# Lamp_Logic_Board_4.net
KiCad netlist of a schematic drawn in EAGLE
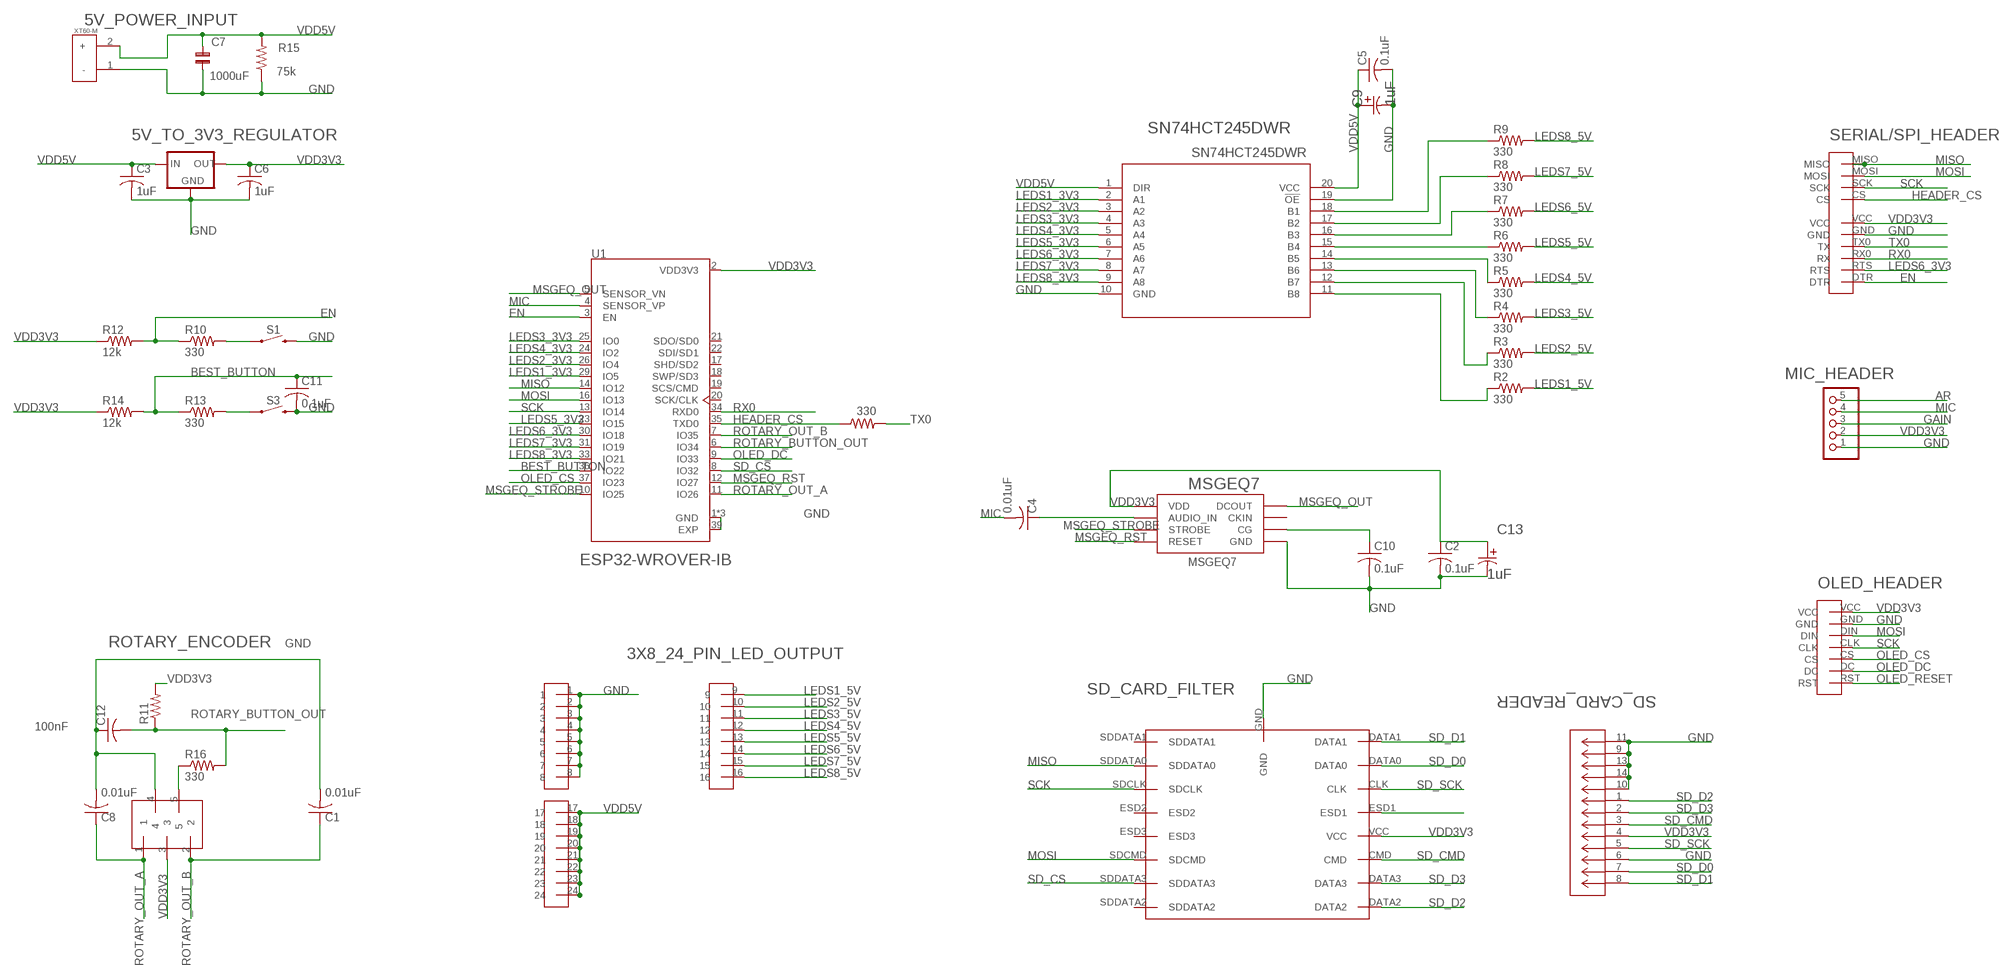
[diagram p0: schematic, sheet 1]

(export (version "E")
  (design (tool "Eeschema 10.0.6"))
  (components
    (comp (ref "3X8_24_PIN_LED_OUTPUT")
      (value "3X8PINHEAD")
      (footprint "eagle-import:3X8PINHEAD")
      (libsource (lib "eagle-import") (part "3X8PINHEAD"))
    )
    (comp (ref "5V_POWER_INPUT")
      (value "XT60-M")
      (footprint "eagle-import:AMASS_XT60-M")
      (fields (field (name "MF") "AMASS"))
      (libsource (lib "eagle-import") (part "XT60-M"))
    )
    (comp (ref "5V_TO_3V3_REGULATOR")
      (value "LM1117MP-1.8")
      (footprint "eagle-import:SOT223")
      (fields (field (name "MF") "Texas Instruments"))
      (libsource (lib "eagle-import") (part "LM1117?-MP1.8"))
    )
    (comp (ref "C1")
      (value "0.01uF")
      (footprint "eagle-import:C0402")
      (libsource (lib "eagle-import") (part "C-USC0402"))
    )
    (comp (ref "C2")
      (value "0.1uF")
      (footprint "eagle-import:C0805")
      (libsource (lib "eagle-import") (part "C-USC0805"))
    )
    (comp (ref "C3")
      (value "1uF")
      (footprint "eagle-import:C0402")
      (libsource (lib "eagle-import") (part "C-USC0402"))
    )
    (comp (ref "C4")
      (value "0.01uF")
      (footprint "eagle-import:C0402")
      (libsource (lib "eagle-import") (part "C-USC0402"))
    )
    (comp (ref "C5")
      (value "0.1uF")
      (footprint "eagle-import:C0805")
      (libsource (lib "eagle-import") (part "C-USC0805"))
    )
    (comp (ref "C6")
      (value "1uF")
      (footprint "eagle-import:C0402")
      (libsource (lib "eagle-import") (part "C-USC0402"))
    )
    (comp (ref "C7")
      (value "1000uF")
      (footprint "eagle-import:ENP2,0-5")
      (libsource (lib "eagle-import") (part "C-BP-2,0X5"))
    )
    (comp (ref "C8")
      (value "0.01uF")
      (footprint "eagle-import:C0402")
      (libsource (lib "eagle-import") (part "C-USC0402"))
    )
    (comp (ref "C9")
      (value "1uF")
      (footprint "eagle-import:CAP_EEFC_B")
      (fields (field (name "MANUFACTURER_PART_NUMBER") "EEEFC1V1R0R"))
      (libsource (lib "eagle-import") (part "EEEFC1V1R0R"))
    )
    (comp (ref "C10")
      (value "0.1uF")
      (footprint "eagle-import:C0805")
      (libsource (lib "eagle-import") (part "C-USC0805"))
    )
    (comp (ref "C11")
      (value "0.1uF")
      (footprint "eagle-import:C0805")
      (libsource (lib "eagle-import") (part "C-USC0805"))
    )
    (comp (ref "C12")
      (value "100nF")
      (footprint "eagle-import:C0402")
      (libsource (lib "eagle-import") (part "C-USC0402"))
    )
    (comp (ref "C13")
      (value "1uF")
      (footprint "eagle-import:CAP_EEFC_B")
      (fields (field (name "MANUFACTURER_PART_NUMBER") "EEEFC1V1R0R"))
      (libsource (lib "eagle-import") (part "EEEFC1V1R0R"))
    )
    (comp (ref "MIC_HEADER")
      (value "PINHD-1X5")
      (footprint "eagle-import:1X05")
      (libsource (lib "eagle-import") (part "PINHD-1X5"))
    )
    (comp (ref "MSGEQ7")
      (value "MSGEQ7DIL")
      (footprint "eagle-import:DIL-08")
      (fields
        (field (name "DIGI-KEY_PART_NUMBER") "1568-1544-ND")
        (field (name "MF") "SparkFun Electronics")
        (field (name "MP") "MSGEQ7")
      )
      (libsource (lib "eagle-import") (part "MSGEQ7DIL"))
    )
    (comp (ref "OLED_HEADER")
      (value "SPIOLED_STANDOFF")
      (footprint "eagle-import:SPIOLED_STADOFF")
      (libsource (lib "eagle-import") (part "SPIOLED_STANDOFF"))
    )
    (comp (ref "R1")
      (value "330")
      (footprint "eagle-import:R1206")
      (libsource (lib "eagle-import") (part "R-US_R1206"))
    )
    (comp (ref "R2")
      (value "330")
      (footprint "eagle-import:R1206")
      (libsource (lib "eagle-import") (part "R-US_R1206"))
    )
    (comp (ref "R3")
      (value "330")
      (footprint "eagle-import:R1206")
      (libsource (lib "eagle-import") (part "R-US_R1206"))
    )
    (comp (ref "R4")
      (value "330")
      (footprint "eagle-import:R1206")
      (libsource (lib "eagle-import") (part "R-US_R1206"))
    )
    (comp (ref "R5")
      (value "330")
      (footprint "eagle-import:R1206")
      (libsource (lib "eagle-import") (part "R-US_R1206"))
    )
    (comp (ref "R6")
      (value "330")
      (footprint "eagle-import:R1206")
      (libsource (lib "eagle-import") (part "R-US_R1206"))
    )
    (comp (ref "R7")
      (value "330")
      (footprint "eagle-import:R1206")
      (libsource (lib "eagle-import") (part "R-US_R1206"))
    )
    (comp (ref "R8")
      (value "330")
      (footprint "eagle-import:R1206")
      (libsource (lib "eagle-import") (part "R-US_R1206"))
    )
    (comp (ref "R9")
      (value "330")
      (footprint "eagle-import:R1206")
      (libsource (lib "eagle-import") (part "R-US_R1206"))
    )
    (comp (ref "R10")
      (value "330")
      (footprint "eagle-import:R1206")
      (libsource (lib "eagle-import") (part "R-US_R1206"))
    )
    (comp (ref "R11")
      (value "R-US_R0603")
      (footprint "eagle-import:R0603")
      (libsource (lib "eagle-import") (part "R-US_R0603"))
    )
    (comp (ref "R12")
      (value "12k")
      (footprint "eagle-import:R0603")
      (libsource (lib "eagle-import") (part "R-US_R0603"))
    )
    (comp (ref "R13")
      (value "330")
      (footprint "eagle-import:R1206")
      (libsource (lib "eagle-import") (part "R-US_R1206"))
    )
    (comp (ref "R14")
      (value "12k")
      (footprint "eagle-import:R0603")
      (libsource (lib "eagle-import") (part "R-US_R0603"))
    )
    (comp (ref "R15")
      (value "75k")
      (footprint "eagle-import:0309_12")
      (libsource (lib "eagle-import") (part "R-US_0309/12"))
    )
    (comp (ref "R16")
      (value "330")
      (footprint "eagle-import:R1206")
      (libsource (lib "eagle-import") (part "R-US_R1206"))
    )
    (comp (ref "ROTARY_ENCODER")
      (value "EN11-HSM1AF15")
      (footprint "eagle-import:EN11-HSM")
      (libsource (lib "eagle-import") (part "EN11-HSM1AF15"))
    )
    (comp (ref "S1")
      (value "MOMENTARY-SWITCH-SPST-SMD-6.0X3.5MM")
      (footprint "eagle-import:TACTILE_SWITCH_SMD_6.0X3.5MM")
      (libsource (lib "eagle-import") (part "MOMENTARY-SWITCH-SPST-SMD-6.0X3.5MM"))
    )
    (comp (ref "S3")
      (value "MOMENTARY-SWITCH-SPST-SMD-12MM")
      (footprint "eagle-import:TACTILE_SWITCH_SMD_12MM")
      (libsource (lib "eagle-import") (part "MOMENTARY-SWITCH-SPST-SMD-12MM"))
    )
    (comp (ref "SD_CARD_FILTER")
      (value "CM1624-08DE")
      (footprint "eagle-import:CM1624-08DE")
      (libsource (lib "eagle-import") (part "CM1624-08DE"))
    )
    (comp (ref "SD_CARD_READER")
      (value "LLC")
      (footprint "eagle-import:CON00218_8")
      (libsource (lib "eagle-import") (part "LLC"))
    )
    (comp (ref "SERIAL/SPI_HEADER")
      (value "2X6PINHEAD")
      (footprint "eagle-import:2X6PINHEAD")
      (libsource (lib "eagle-import") (part "2X6PINHEAD"))
    )
    (comp (ref "SN74HCT245DWR")
      (value "SN74HCT245DWR")
      (footprint "eagle-import:DW20")
      (libsource (lib "eagle-import") (part "SN74HCT245DWR"))
    )
    (comp (ref "U1")
      (value "ESP32-WROVER-IB")
      (footprint "eagle-import:XCVR_ESP32-WROVER-I")
      (fields (field (name "MF") "Espressif Systems") (field (name "MP") "ESP32-WROVER-I"))
      (libsource (lib "eagle-import") (part "ESP32-WROVER-I"))
    )
  )
  (nets
    (net (code "1") (name "AR") (class "Default")
      (node (ref "MIC_HEADER") (pin "5") (pinfunction "5_5") (pintype "passive"))
    )
    (net (code "2") (name "BEST_BUTTON") (class "Default")
      (node (ref "C11") (pin "1") (pinfunction "1_1") (pintype "passive"))
      (node (ref "R13") (pin "1") (pinfunction "1_1") (pintype "passive"))
      (node (ref "R14") (pin "2") (pinfunction "2_2") (pintype "passive"))
      (node (ref "U1") (pin "36") (pinfunction "IO22_36") (pintype "bidirectional"))
    )
    (net (code "3") (name "EN") (class "Default")
      (node (ref "R10") (pin "1") (pinfunction "1_1") (pintype "passive"))
      (node (ref "R12") (pin "2") (pinfunction "2_2") (pintype "passive"))
      (node (ref "SERIAL/SPI_HEADER") (pin "DTR") (pinfunction "DTR_DTR") (pintype "bidirectional"))
      (node (ref "U1") (pin "3") (pinfunction "EN_3") (pintype "input"))
    )
    (net (code "4") (name "GAIN") (class "Default")
      (node (ref "MIC_HEADER") (pin "3") (pinfunction "3_3") (pintype "passive"))
    )
    (net (code "5") (name "GND") (class "Default")
      (node (ref "3X8_24_PIN_LED_OUTPUT") (pin "1") (pinfunction "1_1") (pintype "bidirectional"))
      (node (ref "3X8_24_PIN_LED_OUTPUT") (pin "2") (pinfunction "2_2") (pintype "bidirectional"))
      (node (ref "3X8_24_PIN_LED_OUTPUT") (pin "3") (pinfunction "3_3") (pintype "bidirectional"))
      (node (ref "3X8_24_PIN_LED_OUTPUT") (pin "4") (pinfunction "4_4") (pintype "bidirectional"))
      (node (ref "3X8_24_PIN_LED_OUTPUT") (pin "5") (pinfunction "5_5") (pintype "bidirectional"))
      (node (ref "3X8_24_PIN_LED_OUTPUT") (pin "6") (pinfunction "6_6") (pintype "bidirectional"))
      (node (ref "3X8_24_PIN_LED_OUTPUT") (pin "7") (pinfunction "7_7") (pintype "bidirectional"))
      (node (ref "3X8_24_PIN_LED_OUTPUT") (pin "8") (pinfunction "8_8") (pintype "bidirectional"))
      (node (ref "5V_POWER_INPUT") (pin "1") (pinfunction "-_1") (pintype "passive"))
      (node (ref "5V_TO_3V3_REGULATOR") (pin "1") (pinfunction "GND_1") (pintype "input"))
      (node (ref "C1") (pin "2") (pinfunction "2_2") (pintype "passive"))
      (node (ref "C10") (pin "2") (pinfunction "2_2") (pintype "passive"))
      (node (ref "C11") (pin "2") (pinfunction "2_2") (pintype "passive"))
      (node (ref "C12") (pin "1") (pinfunction "1_1") (pintype "passive"))
      (node (ref "C13") (pin "2") (pinfunction "2_2") (pintype "passive"))
      (node (ref "C2") (pin "2") (pinfunction "2_2") (pintype "passive"))
      (node (ref "C3") (pin "2") (pinfunction "2_2") (pintype "passive"))
      (node (ref "C5") (pin "2") (pinfunction "2_2") (pintype "passive"))
      (node (ref "C6") (pin "2") (pinfunction "2_2") (pintype "passive"))
      (node (ref "C7") (pin "1") (pinfunction "1_1") (pintype "passive"))
      (node (ref "C8") (pin "2") (pinfunction "2_2") (pintype "passive"))
      (node (ref "C9") (pin "2") (pinfunction "2_2") (pintype "passive"))
      (node (ref "MIC_HEADER") (pin "1") (pinfunction "1_1") (pintype "passive"))
      (node (ref "MSGEQ7") (pin "2") (pinfunction "GND_2") (pintype "bidirectional"))
      (node (ref "OLED_HEADER") (pin "GND") (pinfunction "GND_GND") (pintype "bidirectional"))
      (node (ref "R15") (pin "1") (pinfunction "1_1") (pintype "passive"))
      (node (ref "ROTARY_ENCODER") (pin "4") (pinfunction "4_4") (pintype "bidirectional"))
      (node (ref "S1") (pin "2") (pinfunction "2_2") (pintype "passive"))
      (node (ref "S3") (pin "3") (pinfunction "2_3") (pintype "passive"))
      (node (ref "SD_CARD_FILTER") (pin "GND") (pinfunction "GND_GND") (pintype "bidirectional"))
      (node (ref "SD_CARD_READER") (pin "10") (pinfunction "10_10") (pintype "passive"))
      (node (ref "SD_CARD_READER") (pin "11") (pinfunction "11_11") (pintype "passive"))
      (node (ref "SD_CARD_READER") (pin "13") (pinfunction "13_13") (pintype "passive"))
      (node (ref "SD_CARD_READER") (pin "14") (pinfunction "14_14") (pintype "passive"))
      (node (ref "SD_CARD_READER") (pin "6") (pinfunction "6_6") (pintype "passive"))
      (node (ref "SD_CARD_READER") (pin "9") (pinfunction "9_9") (pintype "passive"))
      (node (ref "SERIAL/SPI_HEADER") (pin "GND") (pinfunction "GND_GND") (pintype "bidirectional"))
      (node (ref "SN74HCT245DWR") (pin "10") (pinfunction "GND_10") (pintype "power_in"))
      (node (ref "SN74HCT245DWR") (pin "19") (pinfunction "~{OE}_19") (pintype "input"))
      (node (ref "U1") (pin "1") (pinfunction "GND_1") (pintype "power_in"))
      (node (ref "U1") (pin "15") (pinfunction "GND_15") (pintype "power_in"))
      (node (ref "U1") (pin "38") (pinfunction "GND_38") (pintype "power_in"))
      (node (ref "U1") (pin "39") (pinfunction "EXP_39") (pintype "power_in"))
    )
    (net (code "6") (name "HEADER_CS") (class "Default")
      (node (ref "R1") (pin "1") (pinfunction "1_1") (pintype "passive"))
      (node (ref "SERIAL/SPI_HEADER") (pin "CS") (pinfunction "CS_CS") (pintype "bidirectional"))
      (node (ref "U1") (pin "35") (pinfunction "TXD0_35") (pintype "bidirectional"))
    )
    (net (code "7") (name "LEDS1_3V3") (class "Default")
      (node (ref "SN74HCT245DWR") (pin "2") (pinfunction "A1_2") (pintype "bidirectional"))
      (node (ref "U1") (pin "29") (pinfunction "IO5_29") (pintype "bidirectional"))
    )
    (net (code "8") (name "LEDS1_5V") (class "Default")
      (node (ref "3X8_24_PIN_LED_OUTPUT") (pin "9") (pinfunction "9_9") (pintype "bidirectional"))
      (node (ref "R2") (pin "2") (pinfunction "2_2") (pintype "passive"))
    )
    (net (code "9") (name "LEDS2_3V3") (class "Default")
      (node (ref "SN74HCT245DWR") (pin "3") (pinfunction "A2_3") (pintype "bidirectional"))
      (node (ref "U1") (pin "26") (pinfunction "IO4_26") (pintype "bidirectional"))
    )
    (net (code "10") (name "LEDS2_5V") (class "Default")
      (node (ref "3X8_24_PIN_LED_OUTPUT") (pin "10") (pinfunction "10_10") (pintype "bidirectional"))
      (node (ref "R3") (pin "2") (pinfunction "2_2") (pintype "passive"))
    )
    (net (code "11") (name "LEDS3_3V3") (class "Default")
      (node (ref "SN74HCT245DWR") (pin "4") (pinfunction "A3_4") (pintype "bidirectional"))
      (node (ref "U1") (pin "25") (pinfunction "IO0_25") (pintype "bidirectional"))
    )
    (net (code "12") (name "LEDS3_5V") (class "Default")
      (node (ref "3X8_24_PIN_LED_OUTPUT") (pin "11") (pinfunction "11_11") (pintype "bidirectional"))
      (node (ref "R4") (pin "2") (pinfunction "2_2") (pintype "passive"))
    )
    (net (code "13") (name "LEDS4_3V3") (class "Default")
      (node (ref "SN74HCT245DWR") (pin "5") (pinfunction "A4_5") (pintype "bidirectional"))
      (node (ref "U1") (pin "24") (pinfunction "IO2_24") (pintype "bidirectional"))
    )
    (net (code "14") (name "LEDS4_5V") (class "Default")
      (node (ref "3X8_24_PIN_LED_OUTPUT") (pin "12") (pinfunction "12_12") (pintype "bidirectional"))
      (node (ref "R5") (pin "2") (pinfunction "2_2") (pintype "passive"))
    )
    (net (code "15") (name "LEDS5_3V3") (class "Default")
      (node (ref "SN74HCT245DWR") (pin "6") (pinfunction "A5_6") (pintype "bidirectional"))
      (node (ref "U1") (pin "23") (pinfunction "IO15_23") (pintype "bidirectional"))
    )
    (net (code "16") (name "LEDS5_5V") (class "Default")
      (node (ref "3X8_24_PIN_LED_OUTPUT") (pin "13") (pinfunction "13_13") (pintype "bidirectional"))
      (node (ref "R6") (pin "2") (pinfunction "2_2") (pintype "passive"))
    )
    (net (code "17") (name "LEDS6_3V3") (class "Default")
      (node (ref "SERIAL/SPI_HEADER") (pin "RTS") (pinfunction "RTS_RTS") (pintype "bidirectional"))
      (node (ref "SN74HCT245DWR") (pin "7") (pinfunction "A6_7") (pintype "bidirectional"))
      (node (ref "U1") (pin "30") (pinfunction "IO18_30") (pintype "bidirectional"))
    )
    (net (code "18") (name "LEDS6_5V") (class "Default")
      (node (ref "3X8_24_PIN_LED_OUTPUT") (pin "14") (pinfunction "14_14") (pintype "bidirectional"))
      (node (ref "R7") (pin "2") (pinfunction "2_2") (pintype "passive"))
    )
    (net (code "19") (name "LEDS7_3V3") (class "Default")
      (node (ref "SN74HCT245DWR") (pin "8") (pinfunction "A7_8") (pintype "bidirectional"))
      (node (ref "U1") (pin "31") (pinfunction "IO19_31") (pintype "bidirectional"))
    )
    (net (code "20") (name "LEDS7_5V") (class "Default")
      (node (ref "3X8_24_PIN_LED_OUTPUT") (pin "15") (pinfunction "15_15") (pintype "bidirectional"))
      (node (ref "R8") (pin "2") (pinfunction "2_2") (pintype "passive"))
    )
    (net (code "21") (name "LEDS8_3V3") (class "Default")
      (node (ref "SN74HCT245DWR") (pin "9") (pinfunction "A8_9") (pintype "bidirectional"))
      (node (ref "U1") (pin "33") (pinfunction "IO21_33") (pintype "bidirectional"))
    )
    (net (code "22") (name "LEDS8_5V") (class "Default")
      (node (ref "3X8_24_PIN_LED_OUTPUT") (pin "16") (pinfunction "16_16") (pintype "bidirectional"))
      (node (ref "R9") (pin "2") (pinfunction "2_2") (pintype "passive"))
    )
    (net (code "23") (name "MIC") (class "Default")
      (node (ref "C4") (pin "2") (pinfunction "2_2") (pintype "passive"))
      (node (ref "MIC_HEADER") (pin "4") (pinfunction "4_4") (pintype "passive"))
      (node (ref "U1") (pin "4") (pinfunction "SENSOR_VP_4") (pintype "input"))
    )
    (net (code "24") (name "MISO") (class "Default")
      (node (ref "SD_CARD_FILTER") (pin "SDDATA0") (pinfunction "SDDATA0_SDDATA0") (pintype "bidirectional"))
      (node (ref "SERIAL/SPI_HEADER") (pin "MISO") (pinfunction "MISO_MISO") (pintype "bidirectional"))
      (node (ref "U1") (pin "14") (pinfunction "IO12_14") (pintype "bidirectional"))
    )
    (net (code "25") (name "MOSI") (class "Default")
      (node (ref "OLED_HEADER") (pin "DIN") (pinfunction "DIN_DIN") (pintype "bidirectional"))
      (node (ref "SD_CARD_FILTER") (pin "SDCMD") (pinfunction "SDCMD_SDCMD") (pintype "bidirectional"))
      (node (ref "SERIAL/SPI_HEADER") (pin "MOSI") (pinfunction "MOSI_MOSI") (pintype "bidirectional"))
      (node (ref "U1") (pin "16") (pinfunction "IO13_16") (pintype "bidirectional"))
    )
    (net (code "26") (name "MSGEQ_OUT") (class "Default")
      (node (ref "MSGEQ7") (pin "3") (pinfunction "DCOUT_3") (pintype "bidirectional"))
      (node (ref "U1") (pin "5") (pinfunction "SENSOR_VN_5") (pintype "input"))
    )
    (net (code "27") (name "MSGEQ_RST") (class "Default")
      (node (ref "MSGEQ7") (pin "7") (pinfunction "RESET_7") (pintype "input"))
      (node (ref "U1") (pin "12") (pinfunction "IO27_12") (pintype "bidirectional"))
    )
    (net (code "28") (name "MSGEQ_STROBE") (class "Default")
      (node (ref "MSGEQ7") (pin "4") (pinfunction "STROBE_4") (pintype "input"))
      (node (ref "U1") (pin "10") (pinfunction "IO25_10") (pintype "bidirectional"))
    )
    (net (code "29") (name "Net-(MSGEQ7-AUDIO_IN)") (class "Default")
      (node (ref "C4") (pin "1") (pinfunction "1_1") (pintype "passive"))
      (node (ref "MSGEQ7") (pin "5") (pinfunction "AUDIO_IN_5") (pintype "input"))
    )
    (net (code "30") (name "Net-(MSGEQ7-CG)") (class "Default")
      (node (ref "C10") (pin "1") (pinfunction "1_1") (pintype "passive"))
      (node (ref "MSGEQ7") (pin "6") (pinfunction "CG_6") (pintype "bidirectional"))
    )
    (net (code "31") (name "Net-(R10-Pad2)") (class "Default")
      (node (ref "R10") (pin "2") (pinfunction "2_2") (pintype "passive"))
      (node (ref "S1") (pin "1") (pinfunction "1_1") (pintype "passive"))
    )
    (net (code "32") (name "Net-(R13-Pad2)") (class "Default")
      (node (ref "R13") (pin "2") (pinfunction "2_2") (pintype "passive"))
      (node (ref "S3") (pin "1") (pinfunction "1_1") (pintype "passive"))
    )
    (net (code "33") (name "Net-(R16-Pad1)") (class "Default")
      (node (ref "R16") (pin "1") (pinfunction "1_1") (pintype "passive"))
      (node (ref "ROTARY_ENCODER") (pin "5") (pinfunction "5_5") (pintype "bidirectional"))
    )
    (net (code "34") (name "Net-(SN74HCT245DWR-B1)") (class "Default")
      (node (ref "R9") (pin "1") (pinfunction "1_1") (pintype "passive"))
      (node (ref "SN74HCT245DWR") (pin "18") (pinfunction "B1_18") (pintype "bidirectional"))
    )
    (net (code "35") (name "Net-(SN74HCT245DWR-B2)") (class "Default")
      (node (ref "R8") (pin "1") (pinfunction "1_1") (pintype "passive"))
      (node (ref "SN74HCT245DWR") (pin "17") (pinfunction "B2_17") (pintype "bidirectional"))
    )
    (net (code "36") (name "Net-(SN74HCT245DWR-B3)") (class "Default")
      (node (ref "R7") (pin "1") (pinfunction "1_1") (pintype "passive"))
      (node (ref "SN74HCT245DWR") (pin "16") (pinfunction "B3_16") (pintype "bidirectional"))
    )
    (net (code "37") (name "Net-(SN74HCT245DWR-B4)") (class "Default")
      (node (ref "R6") (pin "1") (pinfunction "1_1") (pintype "passive"))
      (node (ref "SN74HCT245DWR") (pin "15") (pinfunction "B4_15") (pintype "bidirectional"))
    )
    (net (code "38") (name "Net-(SN74HCT245DWR-B5)") (class "Default")
      (node (ref "R5") (pin "1") (pinfunction "1_1") (pintype "passive"))
      (node (ref "SN74HCT245DWR") (pin "14") (pinfunction "B5_14") (pintype "bidirectional"))
    )
    (net (code "39") (name "Net-(SN74HCT245DWR-B6)") (class "Default")
      (node (ref "R4") (pin "1") (pinfunction "1_1") (pintype "passive"))
      (node (ref "SN74HCT245DWR") (pin "13") (pinfunction "B6_13") (pintype "bidirectional"))
    )
    (net (code "40") (name "Net-(SN74HCT245DWR-B7)") (class "Default")
      (node (ref "R3") (pin "1") (pinfunction "1_1") (pintype "passive"))
      (node (ref "SN74HCT245DWR") (pin "12") (pinfunction "B7_12") (pintype "bidirectional"))
    )
    (net (code "41") (name "Net-(SN74HCT245DWR-B8)") (class "Default")
      (node (ref "R2") (pin "1") (pinfunction "1_1") (pintype "passive"))
      (node (ref "SN74HCT245DWR") (pin "11") (pinfunction "B8_11") (pintype "bidirectional"))
    )
    (net (code "42") (name "OLED_CS") (class "Default")
      (node (ref "OLED_HEADER") (pin "CS") (pinfunction "CS_CS") (pintype "bidirectional"))
      (node (ref "U1") (pin "37") (pinfunction "IO23_37") (pintype "bidirectional"))
    )
    (net (code "43") (name "OLED_DC") (class "Default")
      (node (ref "OLED_HEADER") (pin "DC") (pinfunction "DC_DC") (pintype "bidirectional"))
      (node (ref "U1") (pin "9") (pinfunction "IO33_9") (pintype "bidirectional"))
    )
    (net (code "44") (name "OLED_RESET") (class "Default")
      (node (ref "OLED_HEADER") (pin "RST") (pinfunction "RST_RST") (pintype "bidirectional"))
    )
    (net (code "45") (name "ROTARY_BUTTON_OUT") (class "Default")
      (node (ref "C12") (pin "2") (pinfunction "2_2") (pintype "passive"))
      (node (ref "R11") (pin "1") (pinfunction "1_1") (pintype "passive"))
      (node (ref "R16") (pin "2") (pinfunction "2_2") (pintype "passive"))
      (node (ref "U1") (pin "6") (pinfunction "IO34_6") (pintype "input"))
    )
    (net (code "46") (name "ROTARY_OUT_A") (class "Default")
      (node (ref "C8") (pin "1") (pinfunction "1_1") (pintype "passive"))
      (node (ref "ROTARY_ENCODER") (pin "1") (pinfunction "1_1") (pintype "passive"))
      (node (ref "U1") (pin "11") (pinfunction "IO26_11") (pintype "bidirectional"))
    )
    (net (code "47") (name "ROTARY_OUT_B") (class "Default")
      (node (ref "C1") (pin "1") (pinfunction "1_1") (pintype "passive"))
      (node (ref "ROTARY_ENCODER") (pin "2") (pinfunction "2_2") (pintype "passive"))
      (node (ref "U1") (pin "7") (pinfunction "IO35_7") (pintype "input"))
    )
    (net (code "48") (name "RX0") (class "Default")
      (node (ref "SERIAL/SPI_HEADER") (pin "RX0") (pinfunction "RX_RX0") (pintype "bidirectional"))
      (node (ref "U1") (pin "34") (pinfunction "RXD0_34") (pintype "bidirectional"))
    )
    (net (code "49") (name "SCK") (class "Default")
      (node (ref "OLED_HEADER") (pin "CLK") (pinfunction "CLK_CLK") (pintype "bidirectional"))
      (node (ref "SD_CARD_FILTER") (pin "SDCLK") (pinfunction "SDCLK_SDCLK") (pintype "bidirectional"))
      (node (ref "SERIAL/SPI_HEADER") (pin "SCK") (pinfunction "SCK_SCK") (pintype "bidirectional"))
      (node (ref "U1") (pin "13") (pinfunction "IO14_13") (pintype "bidirectional"))
    )
    (net (code "50") (name "SD_CMD") (class "Default")
      (node (ref "SD_CARD_FILTER") (pin "CMD") (pinfunction "CMD_CMD") (pintype "bidirectional"))
      (node (ref "SD_CARD_READER") (pin "3") (pinfunction "3_3") (pintype "passive"))
    )
    (net (code "51") (name "SD_CS") (class "Default")
      (node (ref "SD_CARD_FILTER") (pin "SDDATA3") (pinfunction "SDDATA3_SDDATA3") (pintype "bidirectional"))
      (node (ref "U1") (pin "8") (pinfunction "IO32_8") (pintype "bidirectional"))
    )
    (net (code "52") (name "SD_D0") (class "Default")
      (node (ref "SD_CARD_FILTER") (pin "DATA0") (pinfunction "DATA0_DATA0") (pintype "bidirectional"))
      (node (ref "SD_CARD_READER") (pin "7") (pinfunction "7_7") (pintype "passive"))
    )
    (net (code "53") (name "SD_D1") (class "Default")
      (node (ref "SD_CARD_FILTER") (pin "DATA1") (pinfunction "DATA1_DATA1") (pintype "bidirectional"))
      (node (ref "SD_CARD_READER") (pin "8") (pinfunction "8_8") (pintype "passive"))
    )
    (net (code "54") (name "SD_D2") (class "Default")
      (node (ref "SD_CARD_FILTER") (pin "DATA2") (pinfunction "DATA2_DATA2") (pintype "bidirectional"))
      (node (ref "SD_CARD_READER") (pin "1") (pinfunction "1_1") (pintype "passive"))
    )
    (net (code "55") (name "SD_D3") (class "Default")
      (node (ref "SD_CARD_FILTER") (pin "DATA3") (pinfunction "DATA3_DATA3") (pintype "bidirectional"))
      (node (ref "SD_CARD_READER") (pin "2") (pinfunction "2_2") (pintype "passive"))
    )
    (net (code "56") (name "SD_SCK") (class "Default")
      (node (ref "SD_CARD_FILTER") (pin "CLK") (pinfunction "CLK_CLK") (pintype "bidirectional"))
      (node (ref "SD_CARD_READER") (pin "5") (pinfunction "5_5") (pintype "passive"))
    )
    (net (code "57") (name "TX0") (class "Default")
      (node (ref "R1") (pin "2") (pinfunction "2_2") (pintype "passive"))
      (node (ref "SERIAL/SPI_HEADER") (pin "TX0") (pinfunction "TX_TX0") (pintype "bidirectional"))
    )
    (net (code "58") (name "VDD3V3") (class "Default")
      (node (ref "5V_TO_3V3_REGULATOR") (pin "2") (pinfunction "OUT_2") (pintype "passive"))
      (node (ref "5V_TO_3V3_REGULATOR") (pin "4") (pinfunction "OUT_4") (pintype "passive"))
      (node (ref "C13") (pin "1") (pinfunction "1_1") (pintype "passive"))
      (node (ref "C2") (pin "1") (pinfunction "1_1") (pintype "passive"))
      (node (ref "C6") (pin "1") (pinfunction "1_1") (pintype "passive"))
      (node (ref "MIC_HEADER") (pin "2") (pinfunction "2_2") (pintype "passive"))
      (node (ref "MSGEQ7") (pin "1") (pinfunction "VDD_1") (pintype "input"))
      (node (ref "OLED_HEADER") (pin "VCC") (pinfunction "VCC_VCC") (pintype "bidirectional"))
      (node (ref "R11") (pin "2") (pinfunction "2_2") (pintype "passive"))
      (node (ref "R12") (pin "1") (pinfunction "1_1") (pintype "passive"))
      (node (ref "R14") (pin "1") (pinfunction "1_1") (pintype "passive"))
      (node (ref "ROTARY_ENCODER") (pin "3") (pinfunction "3_3") (pintype "passive"))
      (node (ref "SD_CARD_FILTER") (pin "VCC") (pinfunction "VCC_VCC") (pintype "bidirectional"))
      (node (ref "SD_CARD_READER") (pin "4") (pinfunction "4_4") (pintype "passive"))
      (node (ref "SERIAL/SPI_HEADER") (pin "VCC") (pinfunction "VCC_VCC") (pintype "bidirectional"))
      (node (ref "U1") (pin "2") (pinfunction "VDD3V3_2") (pintype "power_in"))
    )
    (net (code "59") (name "VDD5V") (class "Default")
      (node (ref "3X8_24_PIN_LED_OUTPUT") (pin "17") (pinfunction "17_17") (pintype "bidirectional"))
      (node (ref "3X8_24_PIN_LED_OUTPUT") (pin "18") (pinfunction "18_18") (pintype "bidirectional"))
      (node (ref "3X8_24_PIN_LED_OUTPUT") (pin "19") (pinfunction "19_19") (pintype "bidirectional"))
      (node (ref "3X8_24_PIN_LED_OUTPUT") (pin "20") (pinfunction "20_20") (pintype "bidirectional"))
      (node (ref "3X8_24_PIN_LED_OUTPUT") (pin "21") (pinfunction "21_21") (pintype "bidirectional"))
      (node (ref "3X8_24_PIN_LED_OUTPUT") (pin "22") (pinfunction "22_22") (pintype "bidirectional"))
      (node (ref "3X8_24_PIN_LED_OUTPUT") (pin "23") (pinfunction "23_23") (pintype "bidirectional"))
      (node (ref "3X8_24_PIN_LED_OUTPUT") (pin "24") (pinfunction "24_24") (pintype "bidirectional"))
      (node (ref "5V_POWER_INPUT") (pin "2") (pinfunction "+_2") (pintype "passive"))
      (node (ref "5V_TO_3V3_REGULATOR") (pin "3") (pinfunction "IN_3") (pintype "input"))
      (node (ref "C3") (pin "1") (pinfunction "1_1") (pintype "passive"))
      (node (ref "C5") (pin "1") (pinfunction "1_1") (pintype "passive"))
      (node (ref "C7") (pin "2") (pinfunction "2_2") (pintype "passive"))
      (node (ref "C9") (pin "1") (pinfunction "1_1") (pintype "passive"))
      (node (ref "R15") (pin "2") (pinfunction "2_2") (pintype "passive"))
      (node (ref "SN74HCT245DWR") (pin "1") (pinfunction "DIR_1") (pintype "input"))
      (node (ref "SN74HCT245DWR") (pin "20") (pinfunction "VCC_20") (pintype "power_in"))
    )
    (net (code "60") (name "unconnected-(MSGEQ7-CKIN-Pad8)") (class "Default")
      (node (ref "MSGEQ7") (pin "8") (pinfunction "CKIN_8") (pintype "bidirectional"))
    )
    (net (code "61") (name "unconnected-(SD_CARD_FILTER-PadESD1)") (class "Default")
      (node (ref "SD_CARD_FILTER") (pin "ESD1") (pinfunction "ESD1_ESD1") (pintype "bidirectional"))
    )
    (net (code "62") (name "unconnected-(SD_CARD_FILTER-PadESD2)") (class "Default")
      (node (ref "SD_CARD_FILTER") (pin "ESD2") (pinfunction "ESD2_ESD2") (pintype "bidirectional"))
    )
    (net (code "63") (name "unconnected-(SD_CARD_FILTER-PadESD3)") (class "Default")
      (node (ref "SD_CARD_FILTER") (pin "ESD3") (pinfunction "ESD3_ESD3") (pintype "bidirectional"))
    )
    (net (code "64") (name "unconnected-(SD_CARD_FILTER-PadSDDATA1)") (class "Default")
      (node (ref "SD_CARD_FILTER") (pin "SDDATA1") (pinfunction "SDDATA1_SDDATA1") (pintype "bidirectional"))
    )
    (net (code "65") (name "unconnected-(SD_CARD_FILTER-PadSDDATA2)") (class "Default")
      (node (ref "SD_CARD_FILTER") (pin "SDDATA2") (pinfunction "SDDATA2_SDDATA2") (pintype "bidirectional"))
    )
    (net (code "66") (name "unconnected-(U1-SCK{slash}CLK-Pad20)") (class "Default")
      (node (ref "U1") (pin "20") (pinfunction "SCK/CLK_20") (pintype "bidirectional"))
    )
    (net (code "67") (name "unconnected-(U1-SCS{slash}CMD-Pad19)") (class "Default")
      (node (ref "U1") (pin "19") (pinfunction "SCS/CMD_19") (pintype "bidirectional"))
    )
    (net (code "68") (name "unconnected-(U1-SDI{slash}SD1-Pad22)") (class "Default")
      (node (ref "U1") (pin "22") (pinfunction "SDI/SD1_22") (pintype "bidirectional"))
    )
    (net (code "69") (name "unconnected-(U1-SDO{slash}SD0-Pad21)") (class "Default")
      (node (ref "U1") (pin "21") (pinfunction "SDO/SD0_21") (pintype "bidirectional"))
    )
    (net (code "70") (name "unconnected-(U1-SHD{slash}SD2-Pad17)") (class "Default")
      (node (ref "U1") (pin "17") (pinfunction "SHD/SD2_17") (pintype "bidirectional"))
    )
    (net (code "71") (name "unconnected-(U1-SWP{slash}SD3-Pad18)") (class "Default")
      (node (ref "U1") (pin "18") (pinfunction "SWP/SD3_18") (pintype "bidirectional"))
    )
  )
)
